# ProPrj_measure_boardd_2025-02-12.net
KiCad netlist of a schematic drawn in EasyEDA Pro
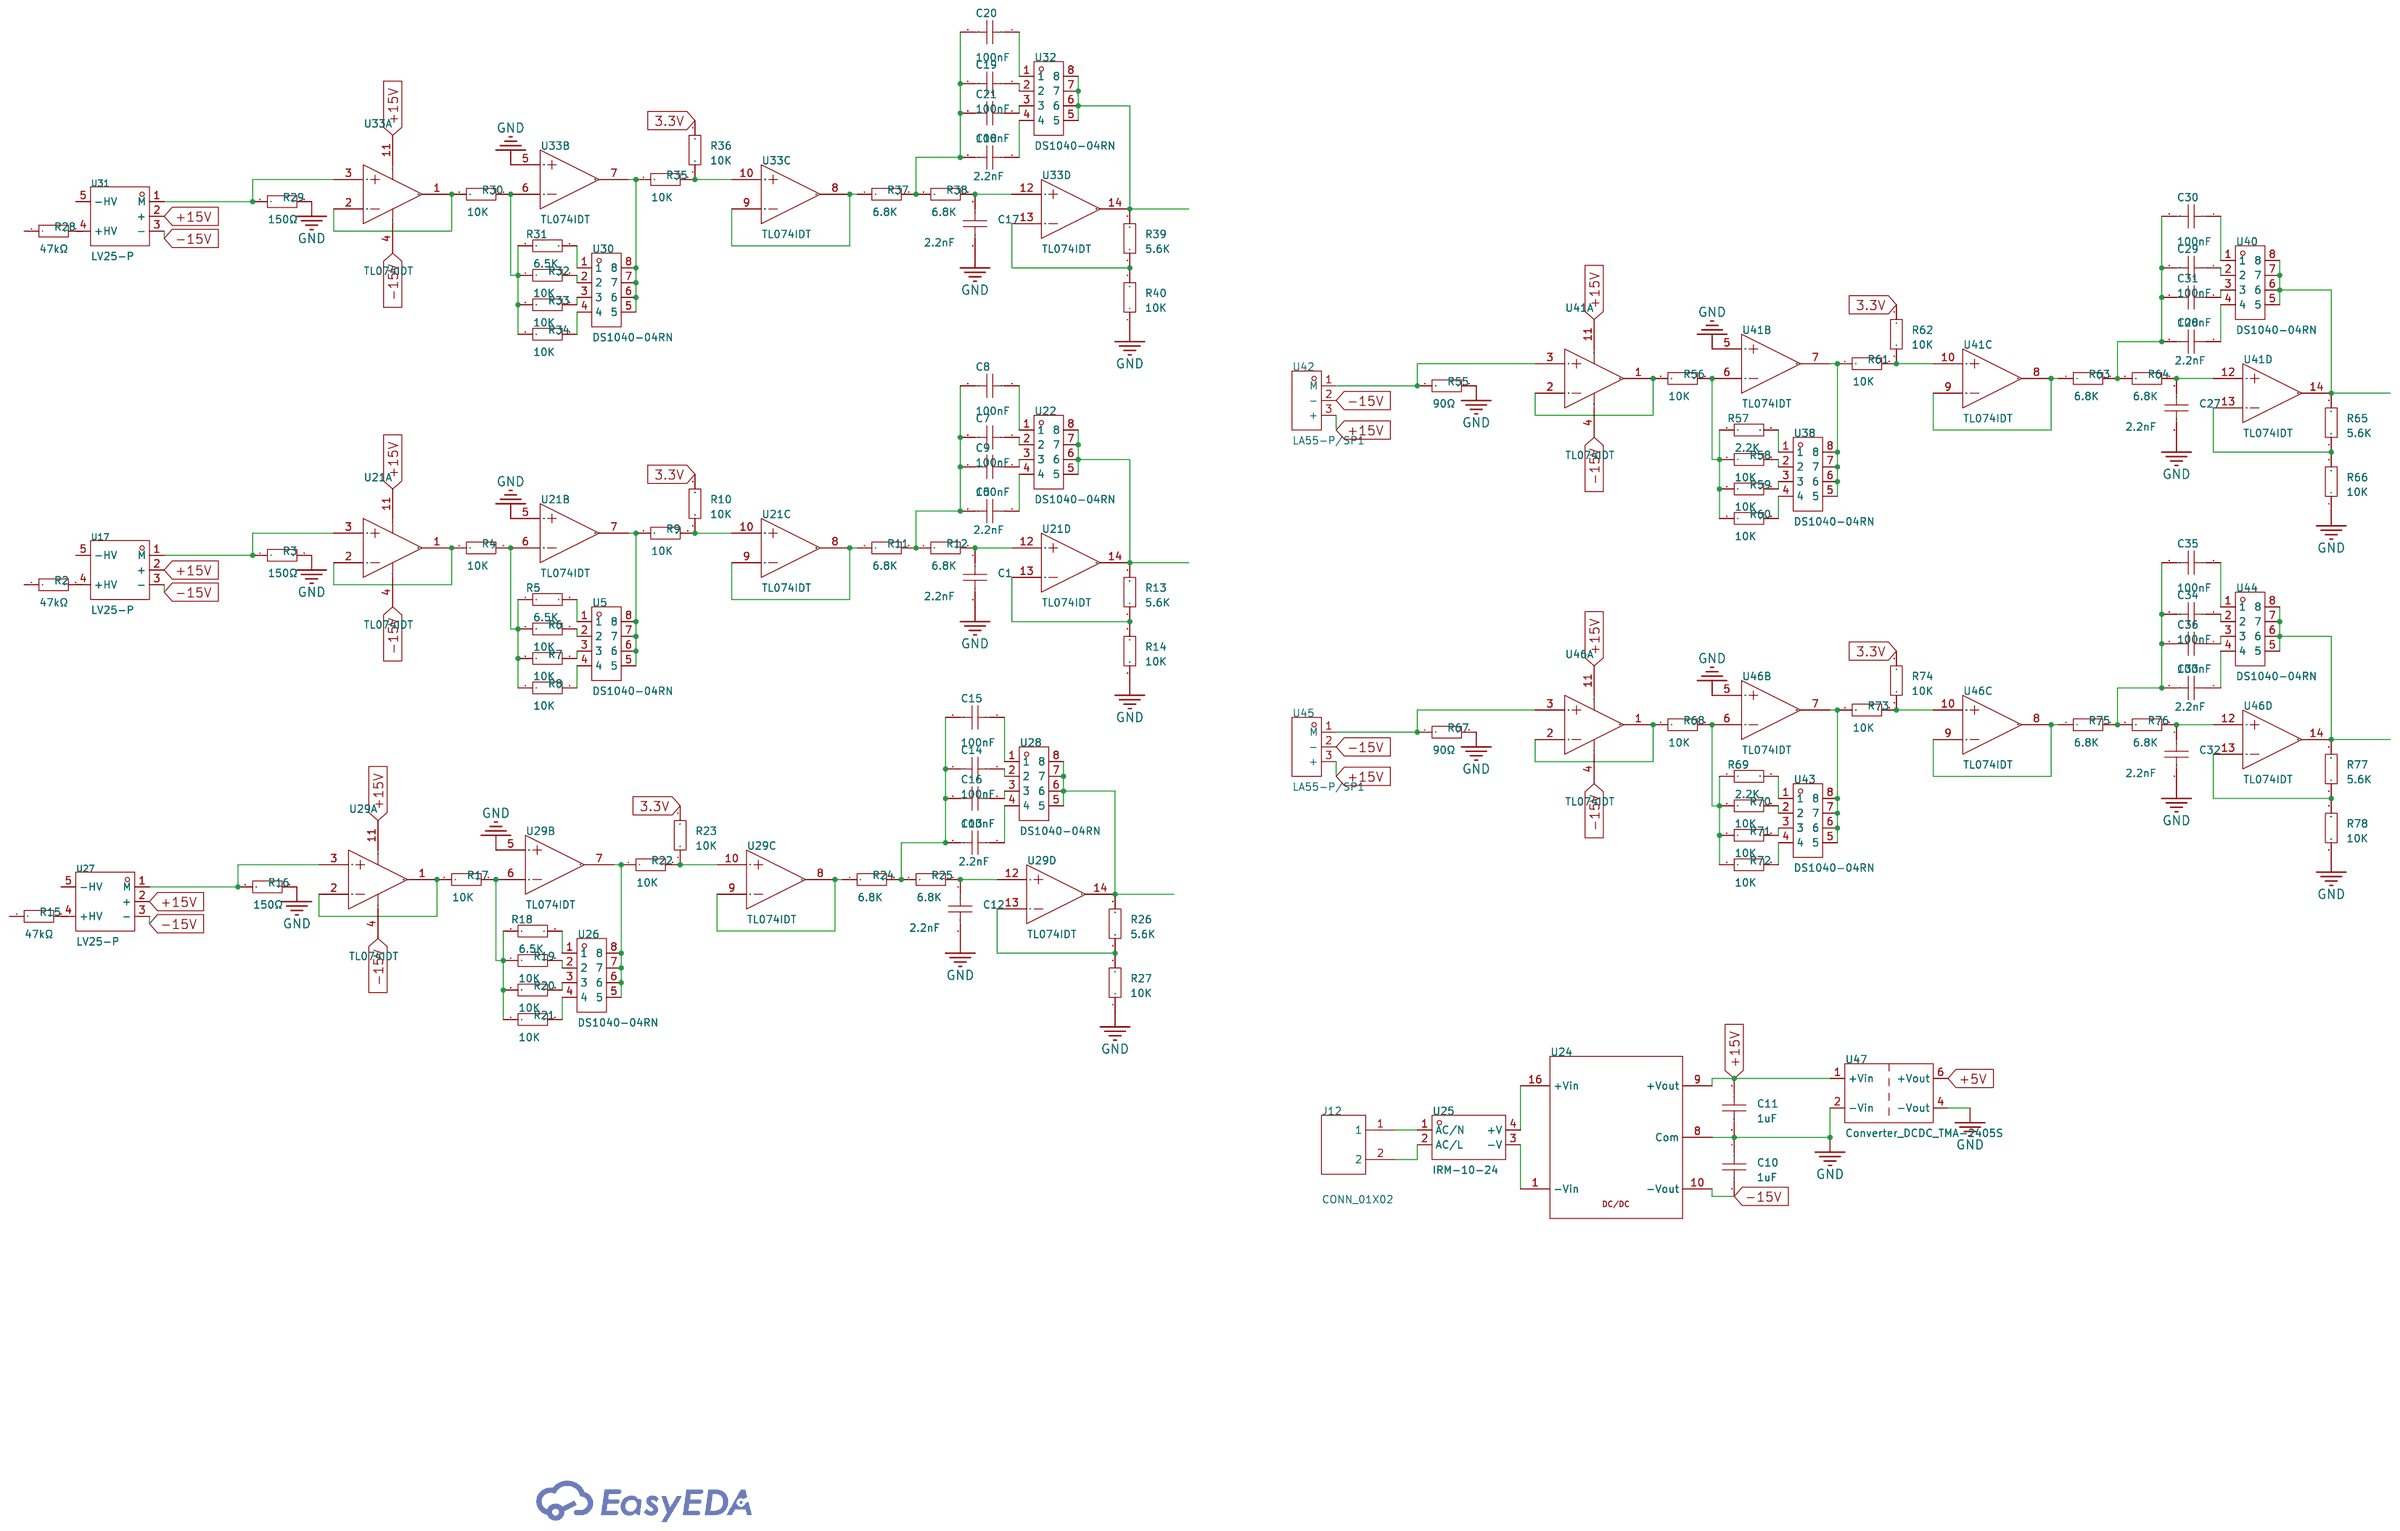
[diagram p0: schematic sheet]

(export (version "E")
  (design (tool "Eeschema 10.0.6"))
  (components
    (comp (ref "C1")
      (value "2.2nF")
      (footprint "easyedapro:C0805")
      (libsource (lib "easyedapro") (part "CAP"))
    )
    (comp (ref "C5")
      (value "2.2nF")
      (footprint "easyedapro:C0805")
      (libsource (lib "easyedapro") (part "CAP"))
    )
    (comp (ref "C7")
      (value "100nF")
      (footprint "easyedapro:C0805")
      (libsource (lib "easyedapro") (part "CAP"))
    )
    (comp (ref "C8")
      (value "100nF")
      (footprint "easyedapro:C0805")
      (libsource (lib "easyedapro") (part "CAP"))
    )
    (comp (ref "C9")
      (value "100nF")
      (footprint "easyedapro:C0805")
      (libsource (lib "easyedapro") (part "CAP"))
    )
    (comp (ref "C10")
      (value "1uF")
      (footprint "easyedapro:C0805")
      (libsource (lib "easyedapro") (part "CAP"))
    )
    (comp (ref "C11")
      (value "1uF")
      (footprint "easyedapro:C0805")
      (libsource (lib "easyedapro") (part "CAP"))
    )
    (comp (ref "C12")
      (value "2.2nF")
      (footprint "easyedapro:C0805")
      (libsource (lib "easyedapro") (part "CAP"))
    )
    (comp (ref "C13")
      (value "2.2nF")
      (footprint "easyedapro:C0805")
      (libsource (lib "easyedapro") (part "CAP"))
    )
    (comp (ref "C14")
      (value "100nF")
      (footprint "easyedapro:C0805")
      (libsource (lib "easyedapro") (part "CAP"))
    )
    (comp (ref "C15")
      (value "100nF")
      (footprint "easyedapro:C0805")
      (libsource (lib "easyedapro") (part "CAP"))
    )
    (comp (ref "C16")
      (value "100nF")
      (footprint "easyedapro:C0805")
      (libsource (lib "easyedapro") (part "CAP"))
    )
    (comp (ref "C17")
      (value "2.2nF")
      (footprint "easyedapro:C0805")
      (libsource (lib "easyedapro") (part "CAP"))
    )
    (comp (ref "C18")
      (value "2.2nF")
      (footprint "easyedapro:C0805")
      (libsource (lib "easyedapro") (part "CAP"))
    )
    (comp (ref "C19")
      (value "100nF")
      (footprint "easyedapro:C0805")
      (libsource (lib "easyedapro") (part "CAP"))
    )
    (comp (ref "C20")
      (value "100nF")
      (footprint "easyedapro:C0805")
      (libsource (lib "easyedapro") (part "CAP"))
    )
    (comp (ref "C21")
      (value "100nF")
      (footprint "easyedapro:C0805")
      (libsource (lib "easyedapro") (part "CAP"))
    )
    (comp (ref "C27")
      (value "2.2nF")
      (footprint "easyedapro:C0805")
      (libsource (lib "easyedapro") (part "CAP"))
    )
    (comp (ref "C28")
      (value "2.2nF")
      (footprint "easyedapro:C0805")
      (libsource (lib "easyedapro") (part "CAP"))
    )
    (comp (ref "C29")
      (value "100nF")
      (footprint "easyedapro:C0805")
      (libsource (lib "easyedapro") (part "CAP"))
    )
    (comp (ref "C30")
      (value "100nF")
      (footprint "easyedapro:C0805")
      (libsource (lib "easyedapro") (part "CAP"))
    )
    (comp (ref "C31")
      (value "100nF")
      (footprint "easyedapro:C0805")
      (libsource (lib "easyedapro") (part "CAP"))
    )
    (comp (ref "C32")
      (value "2.2nF")
      (footprint "easyedapro:C0805")
      (libsource (lib "easyedapro") (part "CAP"))
    )
    (comp (ref "C33")
      (value "2.2nF")
      (footprint "easyedapro:C0805")
      (libsource (lib "easyedapro") (part "CAP"))
    )
    (comp (ref "C34")
      (value "100nF")
      (footprint "easyedapro:C0805")
      (libsource (lib "easyedapro") (part "CAP"))
    )
    (comp (ref "C35")
      (value "100nF")
      (footprint "easyedapro:C0805")
      (libsource (lib "easyedapro") (part "CAP"))
    )
    (comp (ref "C36")
      (value "100nF")
      (footprint "easyedapro:C0805")
      (libsource (lib "easyedapro") (part "CAP"))
    )
    (comp (ref "J12")
      (value "CONN_01X02")
      (footprint "easyedapro:CONN-TH_2P-P3.81_1727010")
      (fields
        (field (name "Manufacturer Part") "1727010")
        (field (name "Manufacturer") "Phoenix Contact(菲尼克斯)")
      )
      (libsource (lib "easyedapro") (part "MKDS1/2-3.81-1727010"))
    )
    (comp (ref "R2")
      (value "47kΩ")
      (footprint "easyedapro:RES-TH_BD8.0-L24.5-P28.50-D0.8")
      (libsource (lib "easyedapro") (part "Res"))
    )
    (comp (ref "R3")
      (value "150Ω")
      (footprint "easyedapro:RES-TH_BD8.0-L24.5-P28.50-D0.8")
      (libsource (lib "easyedapro") (part "Res"))
    )
    (comp (ref "R4")
      (value "10K")
      (footprint "easyedapro:RES-TH_BD8.0-L24.5-P28.50-D0.8")
      (libsource (lib "easyedapro") (part "Res"))
    )
    (comp (ref "R5")
      (value "6.5K")
      (footprint "easyedapro:RES-TH_BD8.0-L24.5-P28.50-D0.8")
      (libsource (lib "easyedapro") (part "Res"))
    )
    (comp (ref "R6")
      (value "10K")
      (footprint "easyedapro:RES-TH_BD8.0-L24.5-P28.50-D0.8")
      (libsource (lib "easyedapro") (part "Res"))
    )
    (comp (ref "R7")
      (value "10K")
      (footprint "easyedapro:RES-TH_BD8.0-L24.5-P28.50-D0.8")
      (libsource (lib "easyedapro") (part "Res"))
    )
    (comp (ref "R8")
      (value "10K")
      (footprint "easyedapro:RES-TH_BD8.0-L24.5-P28.50-D0.8")
      (libsource (lib "easyedapro") (part "Res"))
    )
    (comp (ref "R9")
      (value "10K")
      (footprint "easyedapro:RES-TH_BD8.0-L24.5-P28.50-D0.8")
      (libsource (lib "easyedapro") (part "Res"))
    )
    (comp (ref "R10")
      (value "10K")
      (footprint "easyedapro:RES-TH_BD8.0-L24.5-P28.50-D0.8")
      (libsource (lib "easyedapro") (part "Res"))
    )
    (comp (ref "R11")
      (value "6.8K")
      (footprint "easyedapro:RES-TH_BD8.0-L24.5-P28.50-D0.8")
      (libsource (lib "easyedapro") (part "Res"))
    )
    (comp (ref "R12")
      (value "6.8K")
      (footprint "easyedapro:RES-TH_BD8.0-L24.5-P28.50-D0.8")
      (libsource (lib "easyedapro") (part "Res"))
    )
    (comp (ref "R13")
      (value "5.6K")
      (footprint "easyedapro:RES-TH_BD8.0-L24.5-P28.50-D0.8")
      (libsource (lib "easyedapro") (part "Res"))
    )
    (comp (ref "R14")
      (value "10K")
      (footprint "easyedapro:RES-TH_BD8.0-L24.5-P28.50-D0.8")
      (libsource (lib "easyedapro") (part "Res"))
    )
    (comp (ref "R15")
      (value "47kΩ")
      (footprint "easyedapro:RES-TH_BD8.0-L24.5-P28.50-D0.8")
      (libsource (lib "easyedapro") (part "Res"))
    )
    (comp (ref "R16")
      (value "150Ω")
      (footprint "easyedapro:RES-TH_BD8.0-L24.5-P28.50-D0.8")
      (libsource (lib "easyedapro") (part "Res"))
    )
    (comp (ref "R17")
      (value "10K")
      (footprint "easyedapro:RES-TH_BD8.0-L24.5-P28.50-D0.8")
      (libsource (lib "easyedapro") (part "Res"))
    )
    (comp (ref "R18")
      (value "6.5K")
      (footprint "easyedapro:RES-TH_BD8.0-L24.5-P28.50-D0.8")
      (libsource (lib "easyedapro") (part "Res"))
    )
    (comp (ref "R19")
      (value "10K")
      (footprint "easyedapro:RES-TH_BD8.0-L24.5-P28.50-D0.8")
      (libsource (lib "easyedapro") (part "Res"))
    )
    (comp (ref "R20")
      (value "10K")
      (footprint "easyedapro:RES-TH_BD8.0-L24.5-P28.50-D0.8")
      (libsource (lib "easyedapro") (part "Res"))
    )
    (comp (ref "R21")
      (value "10K")
      (footprint "easyedapro:RES-TH_BD8.0-L24.5-P28.50-D0.8")
      (libsource (lib "easyedapro") (part "Res"))
    )
    (comp (ref "R22")
      (value "10K")
      (footprint "easyedapro:RES-TH_BD8.0-L24.5-P28.50-D0.8")
      (libsource (lib "easyedapro") (part "Res"))
    )
    (comp (ref "R23")
      (value "10K")
      (footprint "easyedapro:RES-TH_BD8.0-L24.5-P28.50-D0.8")
      (libsource (lib "easyedapro") (part "Res"))
    )
    (comp (ref "R24")
      (value "6.8K")
      (footprint "easyedapro:RES-TH_BD8.0-L24.5-P28.50-D0.8")
      (libsource (lib "easyedapro") (part "Res"))
    )
    (comp (ref "R25")
      (value "6.8K")
      (footprint "easyedapro:RES-TH_BD8.0-L24.5-P28.50-D0.8")
      (libsource (lib "easyedapro") (part "Res"))
    )
    (comp (ref "R26")
      (value "5.6K")
      (footprint "easyedapro:RES-TH_BD8.0-L24.5-P28.50-D0.8")
      (libsource (lib "easyedapro") (part "Res"))
    )
    (comp (ref "R27")
      (value "10K")
      (footprint "easyedapro:RES-TH_BD8.0-L24.5-P28.50-D0.8")
      (libsource (lib "easyedapro") (part "Res"))
    )
    (comp (ref "R28")
      (value "47kΩ")
      (footprint "easyedapro:RES-TH_BD8.0-L24.5-P28.50-D0.8")
      (libsource (lib "easyedapro") (part "Res"))
    )
    (comp (ref "R29")
      (value "150Ω")
      (footprint "easyedapro:RES-TH_BD8.0-L24.5-P28.50-D0.8")
      (libsource (lib "easyedapro") (part "Res"))
    )
    (comp (ref "R30")
      (value "10K")
      (footprint "easyedapro:RES-TH_BD8.0-L24.5-P28.50-D0.8")
      (libsource (lib "easyedapro") (part "Res"))
    )
    (comp (ref "R31")
      (value "6.5K")
      (footprint "easyedapro:RES-TH_BD8.0-L24.5-P28.50-D0.8")
      (libsource (lib "easyedapro") (part "Res"))
    )
    (comp (ref "R32")
      (value "10K")
      (footprint "easyedapro:RES-TH_BD8.0-L24.5-P28.50-D0.8")
      (libsource (lib "easyedapro") (part "Res"))
    )
    (comp (ref "R33")
      (value "10K")
      (footprint "easyedapro:RES-TH_BD8.0-L24.5-P28.50-D0.8")
      (libsource (lib "easyedapro") (part "Res"))
    )
    (comp (ref "R34")
      (value "10K")
      (footprint "easyedapro:RES-TH_BD8.0-L24.5-P28.50-D0.8")
      (libsource (lib "easyedapro") (part "Res"))
    )
    (comp (ref "R35")
      (value "10K")
      (footprint "easyedapro:RES-TH_BD8.0-L24.5-P28.50-D0.8")
      (libsource (lib "easyedapro") (part "Res"))
    )
    (comp (ref "R36")
      (value "10K")
      (footprint "easyedapro:RES-TH_BD8.0-L24.5-P28.50-D0.8")
      (libsource (lib "easyedapro") (part "Res"))
    )
    (comp (ref "R37")
      (value "6.8K")
      (footprint "easyedapro:RES-TH_BD8.0-L24.5-P28.50-D0.8")
      (libsource (lib "easyedapro") (part "Res"))
    )
    (comp (ref "R38")
      (value "6.8K")
      (footprint "easyedapro:RES-TH_BD8.0-L24.5-P28.50-D0.8")
      (libsource (lib "easyedapro") (part "Res"))
    )
    (comp (ref "R39")
      (value "5.6K")
      (footprint "easyedapro:RES-TH_BD8.0-L24.5-P28.50-D0.8")
      (libsource (lib "easyedapro") (part "Res"))
    )
    (comp (ref "R40")
      (value "10K")
      (footprint "easyedapro:RES-TH_BD8.0-L24.5-P28.50-D0.8")
      (libsource (lib "easyedapro") (part "Res"))
    )
    (comp (ref "R55")
      (value "90Ω")
      (footprint "easyedapro:RES-TH_BD8.0-L24.5-P28.50-D0.8")
      (libsource (lib "easyedapro") (part "Res"))
    )
    (comp (ref "R56")
      (value "10K")
      (footprint "easyedapro:RES-TH_BD8.0-L24.5-P28.50-D0.8")
      (libsource (lib "easyedapro") (part "Res"))
    )
    (comp (ref "R57")
      (value "2.2K")
      (footprint "easyedapro:RES-TH_BD8.0-L24.5-P28.50-D0.8")
      (libsource (lib "easyedapro") (part "Res"))
    )
    (comp (ref "R58")
      (value "10K")
      (footprint "easyedapro:RES-TH_BD8.0-L24.5-P28.50-D0.8")
      (libsource (lib "easyedapro") (part "Res"))
    )
    (comp (ref "R59")
      (value "10K")
      (footprint "easyedapro:RES-TH_BD8.0-L24.5-P28.50-D0.8")
      (libsource (lib "easyedapro") (part "Res"))
    )
    (comp (ref "R60")
      (value "10K")
      (footprint "easyedapro:RES-TH_BD8.0-L24.5-P28.50-D0.8")
      (libsource (lib "easyedapro") (part "Res"))
    )
    (comp (ref "R61")
      (value "10K")
      (footprint "easyedapro:RES-TH_BD8.0-L24.5-P28.50-D0.8")
      (libsource (lib "easyedapro") (part "Res"))
    )
    (comp (ref "R62")
      (value "10K")
      (footprint "easyedapro:RES-TH_BD8.0-L24.5-P28.50-D0.8")
      (libsource (lib "easyedapro") (part "Res"))
    )
    (comp (ref "R63")
      (value "6.8K")
      (footprint "easyedapro:RES-TH_BD8.0-L24.5-P28.50-D0.8")
      (libsource (lib "easyedapro") (part "Res"))
    )
    (comp (ref "R64")
      (value "6.8K")
      (footprint "easyedapro:RES-TH_BD8.0-L24.5-P28.50-D0.8")
      (libsource (lib "easyedapro") (part "Res"))
    )
    (comp (ref "R65")
      (value "5.6K")
      (footprint "easyedapro:RES-TH_BD8.0-L24.5-P28.50-D0.8")
      (libsource (lib "easyedapro") (part "Res"))
    )
    (comp (ref "R66")
      (value "10K")
      (footprint "easyedapro:RES-TH_BD8.0-L24.5-P28.50-D0.8")
      (libsource (lib "easyedapro") (part "Res"))
    )
    (comp (ref "R67")
      (value "90Ω")
      (footprint "easyedapro:RES-TH_BD8.0-L24.5-P28.50-D0.8")
      (libsource (lib "easyedapro") (part "Res"))
    )
    (comp (ref "R68")
      (value "10K")
      (footprint "easyedapro:RES-TH_BD8.0-L24.5-P28.50-D0.8")
      (libsource (lib "easyedapro") (part "Res"))
    )
    (comp (ref "R69")
      (value "2.2K")
      (footprint "easyedapro:RES-TH_BD8.0-L24.5-P28.50-D0.8")
      (libsource (lib "easyedapro") (part "Res"))
    )
    (comp (ref "R70")
      (value "10K")
      (footprint "easyedapro:RES-TH_BD8.0-L24.5-P28.50-D0.8")
      (libsource (lib "easyedapro") (part "Res"))
    )
    (comp (ref "R71")
      (value "10K")
      (footprint "easyedapro:RES-TH_BD8.0-L24.5-P28.50-D0.8")
      (libsource (lib "easyedapro") (part "Res"))
    )
    (comp (ref "R72")
      (value "10K")
      (footprint "easyedapro:RES-TH_BD8.0-L24.5-P28.50-D0.8")
      (libsource (lib "easyedapro") (part "Res"))
    )
    (comp (ref "R73")
      (value "10K")
      (footprint "easyedapro:RES-TH_BD8.0-L24.5-P28.50-D0.8")
      (libsource (lib "easyedapro") (part "Res"))
    )
    (comp (ref "R74")
      (value "10K")
      (footprint "easyedapro:RES-TH_BD8.0-L24.5-P28.50-D0.8")
      (libsource (lib "easyedapro") (part "Res"))
    )
    (comp (ref "R75")
      (value "6.8K")
      (footprint "easyedapro:RES-TH_BD8.0-L24.5-P28.50-D0.8")
      (libsource (lib "easyedapro") (part "Res"))
    )
    (comp (ref "R76")
      (value "6.8K")
      (footprint "easyedapro:RES-TH_BD8.0-L24.5-P28.50-D0.8")
      (libsource (lib "easyedapro") (part "Res"))
    )
    (comp (ref "R77")
      (value "5.6K")
      (footprint "easyedapro:RES-TH_BD8.0-L24.5-P28.50-D0.8")
      (libsource (lib "easyedapro") (part "Res"))
    )
    (comp (ref "R78")
      (value "10K")
      (footprint "easyedapro:RES-TH_BD8.0-L24.5-P28.50-D0.8")
      (libsource (lib "easyedapro") (part "Res"))
    )
    (comp (ref "U5")
      (value "DS1040-04RN")
      (footprint "easyedapro:KEY-TH_DS1040-04RN")
      (description "Number of Positions:4Bit Lead Pitch:2.54mm Color:Red")
      (fields (field (name "Manufacturer") "CONNFLY"))
      (libsource (lib "easyedapro") (part "DS1040-04RN"))
    )
    (comp (ref "U17")
      (value "LV25-P")
      (footprint "easyedapro:SENSOR-TH_LV25-P")
      (fields (field (name "Manufacturer") "LEM(莱姆)"))
      (libsource (lib "easyedapro") (part "LV25-P"))
    )
    (comp (ref "U21")
      (value "TL074IDT")
      (footprint "easyedapro:SOIC-14_L8.7-W3.9-P1.27-LS6.0-BL")
      (fields (field (name "Manufacturer") "ST(意法半导体)"))
      (libsource (lib "easyedapro") (part "TL074IDT"))
    )
    (comp (ref "U22")
      (value "DS1040-04RN")
      (footprint "easyedapro:KEY-TH_DS1040-04RN")
      (description "Number of Positions:4Bit Lead Pitch:2.54mm Color:Red")
      (fields (field (name "Manufacturer") "CONNFLY"))
      (libsource (lib "easyedapro") (part "DS1040-04RN"))
    )
    (comp (ref "U24")
      (value "~")
      (footprint "easyedapro:TEL_8_SERIES")
      (libsource (lib "easyedapro") (part "TEL_8-2423"))
    )
    (comp (ref "U25")
      (value "IRM-10-24")
      (footprint "easyedapro:PWRM-TH_4P-L45.7-W25.4-P8.0")
      (fields (field (name "Manufacturer") "MW(明纬)"))
      (libsource (lib "easyedapro") (part "IRM-10-24_C5127809"))
    )
    (comp (ref "U26")
      (value "DS1040-04RN")
      (footprint "easyedapro:KEY-TH_DS1040-04RN")
      (description "Number of Positions:4Bit Lead Pitch:2.54mm Color:Red")
      (fields (field (name "Manufacturer") "CONNFLY"))
      (libsource (lib "easyedapro") (part "DS1040-04RN"))
    )
    (comp (ref "U27")
      (value "LV25-P")
      (footprint "easyedapro:SENSOR-TH_LV25-P")
      (fields (field (name "Manufacturer") "LEM(莱姆)"))
      (libsource (lib "easyedapro") (part "LV25-P"))
    )
    (comp (ref "U28")
      (value "DS1040-04RN")
      (footprint "easyedapro:KEY-TH_DS1040-04RN")
      (description "Number of Positions:4Bit Lead Pitch:2.54mm Color:Red")
      (fields (field (name "Manufacturer") "CONNFLY"))
      (libsource (lib "easyedapro") (part "DS1040-04RN"))
    )
    (comp (ref "U29")
      (value "TL074IDT")
      (footprint "easyedapro:SOIC-14_L8.7-W3.9-P1.27-LS6.0-BL")
      (fields (field (name "Manufacturer") "ST(意法半导体)"))
      (libsource (lib "easyedapro") (part "TL074IDT"))
    )
    (comp (ref "U30")
      (value "DS1040-04RN")
      (footprint "easyedapro:KEY-TH_DS1040-04RN")
      (description "Number of Positions:4Bit Lead Pitch:2.54mm Color:Red")
      (fields (field (name "Manufacturer") "CONNFLY"))
      (libsource (lib "easyedapro") (part "DS1040-04RN"))
    )
    (comp (ref "U31")
      (value "LV25-P")
      (footprint "easyedapro:SENSOR-TH_LV25-P")
      (fields (field (name "Manufacturer") "LEM(莱姆)"))
      (libsource (lib "easyedapro") (part "LV25-P"))
    )
    (comp (ref "U32")
      (value "DS1040-04RN")
      (footprint "easyedapro:KEY-TH_DS1040-04RN")
      (description "Number of Positions:4Bit Lead Pitch:2.54mm Color:Red")
      (fields (field (name "Manufacturer") "CONNFLY"))
      (libsource (lib "easyedapro") (part "DS1040-04RN"))
    )
    (comp (ref "U33")
      (value "TL074IDT")
      (footprint "easyedapro:SOIC-14_L8.7-W3.9-P1.27-LS6.0-BL")
      (fields (field (name "Manufacturer") "ST(意法半导体)"))
      (libsource (lib "easyedapro") (part "TL074IDT"))
    )
    (comp (ref "U38")
      (value "DS1040-04RN")
      (footprint "easyedapro:KEY-TH_DS1040-04RN")
      (description "Number of Positions:4Bit Lead Pitch:2.54mm Color:Red")
      (fields (field (name "Manufacturer") "CONNFLY"))
      (libsource (lib "easyedapro") (part "DS1040-04RN"))
    )
    (comp (ref "U40")
      (value "DS1040-04RN")
      (footprint "easyedapro:KEY-TH_DS1040-04RN")
      (description "Number of Positions:4Bit Lead Pitch:2.54mm Color:Red")
      (fields (field (name "Manufacturer") "CONNFLY"))
      (libsource (lib "easyedapro") (part "DS1040-04RN"))
    )
    (comp (ref "U41")
      (value "TL074IDT")
      (footprint "easyedapro:SOIC-14_L8.7-W3.9-P1.27-LS6.0-BL")
      (fields (field (name "Manufacturer") "ST(意法半导体)"))
      (libsource (lib "easyedapro") (part "TL074IDT"))
    )
    (comp (ref "U42")
      (value "LA55-P/SP1")
      (footprint "easyedapro:SENSOR-TH_LAXX-P")
      (fields (field (name "Manufacturer") "LEM(莱姆)"))
      (libsource (lib "easyedapro") (part "LA55-P/SP1"))
    )
    (comp (ref "U43")
      (value "DS1040-04RN")
      (footprint "easyedapro:KEY-TH_DS1040-04RN")
      (description "Number of Positions:4Bit Lead Pitch:2.54mm Color:Red")
      (fields (field (name "Manufacturer") "CONNFLY"))
      (libsource (lib "easyedapro") (part "DS1040-04RN"))
    )
    (comp (ref "U44")
      (value "DS1040-04RN")
      (footprint "easyedapro:KEY-TH_DS1040-04RN")
      (description "Number of Positions:4Bit Lead Pitch:2.54mm Color:Red")
      (fields (field (name "Manufacturer") "CONNFLY"))
      (libsource (lib "easyedapro") (part "DS1040-04RN"))
    )
    (comp (ref "U45")
      (value "LA55-P/SP1")
      (footprint "easyedapro:SENSOR-TH_LAXX-P")
      (fields (field (name "Manufacturer") "LEM(莱姆)"))
      (libsource (lib "easyedapro") (part "LA55-P/SP1"))
    )
    (comp (ref "U46")
      (value "TL074IDT")
      (footprint "easyedapro:SOIC-14_L8.7-W3.9-P1.27-LS6.0-BL")
      (fields (field (name "Manufacturer") "ST(意法半导体)"))
      (libsource (lib "easyedapro") (part "TL074IDT"))
    )
    (comp (ref "U47")
      (value "TMA-2405S")
      (footprint "easyedapro:Converter_DCDC:Converter_DCDC_TRACO_TMA-15xxS_24xxS_Single_THT")
      (libsource (lib "easyedapro") (part "Converter_DCDC_TMA-2405S"))
    )
  )
  (nets
    (net (code "1") (name "+5V") (class "Default")
      (node (ref "U47") (pin "6") (pinfunction "+Vout_6") (pintype "unspecified"))
    )
    (net (code "2") (name "+15V") (class "Default")
      (node (ref "C11") (pin "1") (pinfunction "1_1") (pintype "input"))
      (node (ref "U17") (pin "2") (pinfunction "+_2") (pintype "input"))
      (node (ref "U21") (pin "11") (pinfunction "VCC-_11") (pintype "unspecified"))
      (node (ref "U24") (pin "9") (pinfunction "+Vout_9") (pintype "unspecified"))
      (node (ref "U27") (pin "2") (pinfunction "+_2") (pintype "input"))
      (node (ref "U29") (pin "11") (pinfunction "VCC-_11") (pintype "unspecified"))
      (node (ref "U31") (pin "2") (pinfunction "+_2") (pintype "input"))
      (node (ref "U33") (pin "11") (pinfunction "VCC-_11") (pintype "unspecified"))
      (node (ref "U41") (pin "11") (pinfunction "VCC-_11") (pintype "unspecified"))
      (node (ref "U42") (pin "3") (pinfunction "+_3") (pintype "input"))
      (node (ref "U45") (pin "3") (pinfunction "+_3") (pintype "input"))
      (node (ref "U46") (pin "11") (pinfunction "VCC-_11") (pintype "unspecified"))
      (node (ref "U47") (pin "1") (pinfunction "+Vin_1") (pintype "unspecified"))
    )
    (net (code "3") (name "-15V") (class "Default")
      (node (ref "C10") (pin "2") (pinfunction "2_2") (pintype "input"))
      (node (ref "U17") (pin "3") (pinfunction "-_3") (pintype "input"))
      (node (ref "U21") (pin "4") (pinfunction "VCC+_4") (pintype "unspecified"))
      (node (ref "U24") (pin "10") (pinfunction "-Vout_10") (pintype "unspecified"))
      (node (ref "U27") (pin "3") (pinfunction "-_3") (pintype "input"))
      (node (ref "U29") (pin "4") (pinfunction "VCC+_4") (pintype "unspecified"))
      (node (ref "U31") (pin "3") (pinfunction "-_3") (pintype "input"))
      (node (ref "U33") (pin "4") (pinfunction "VCC+_4") (pintype "unspecified"))
      (node (ref "U41") (pin "4") (pinfunction "VCC+_4") (pintype "unspecified"))
      (node (ref "U42") (pin "2") (pinfunction "-_2") (pintype "input"))
      (node (ref "U45") (pin "2") (pinfunction "-_2") (pintype "input"))
      (node (ref "U46") (pin "4") (pinfunction "VCC+_4") (pintype "unspecified"))
    )
    (net (code "4") (name "3.3V") (class "Default")
      (node (ref "R10") (pin "2") (pinfunction "2_2") (pintype "input"))
      (node (ref "R23") (pin "2") (pinfunction "2_2") (pintype "input"))
      (node (ref "R36") (pin "2") (pinfunction "2_2") (pintype "input"))
      (node (ref "R62") (pin "2") (pinfunction "2_2") (pintype "input"))
      (node (ref "R74") (pin "2") (pinfunction "2_2") (pintype "input"))
    )
    (net (code "5") (name "GND") (class "Default")
      (node (ref "C1") (pin "2") (pinfunction "2_2") (pintype "input"))
      (node (ref "C10") (pin "1") (pinfunction "1_1") (pintype "input"))
      (node (ref "C11") (pin "2") (pinfunction "2_2") (pintype "input"))
      (node (ref "C12") (pin "2") (pinfunction "2_2") (pintype "input"))
      (node (ref "C17") (pin "2") (pinfunction "2_2") (pintype "input"))
      (node (ref "C27") (pin "2") (pinfunction "2_2") (pintype "input"))
      (node (ref "C32") (pin "2") (pinfunction "2_2") (pintype "input"))
      (node (ref "R14") (pin "1") (pinfunction "1_1") (pintype "input"))
      (node (ref "R16") (pin "2") (pinfunction "2_2") (pintype "input"))
      (node (ref "R27") (pin "1") (pinfunction "1_1") (pintype "input"))
      (node (ref "R29") (pin "2") (pinfunction "2_2") (pintype "input"))
      (node (ref "R3") (pin "2") (pinfunction "2_2") (pintype "input"))
      (node (ref "R40") (pin "1") (pinfunction "1_1") (pintype "input"))
      (node (ref "R55") (pin "2") (pinfunction "2_2") (pintype "input"))
      (node (ref "R66") (pin "1") (pinfunction "1_1") (pintype "input"))
      (node (ref "R67") (pin "2") (pinfunction "2_2") (pintype "input"))
      (node (ref "R78") (pin "1") (pinfunction "1_1") (pintype "input"))
      (node (ref "U21") (pin "5") (pinfunction "2IN+_5") (pintype "unspecified"))
      (node (ref "U24") (pin "8") (pinfunction "Com_8") (pintype "unspecified"))
      (node (ref "U29") (pin "5") (pinfunction "2IN+_5") (pintype "unspecified"))
      (node (ref "U33") (pin "5") (pinfunction "2IN+_5") (pintype "unspecified"))
      (node (ref "U41") (pin "5") (pinfunction "2IN+_5") (pintype "unspecified"))
      (node (ref "U46") (pin "5") (pinfunction "2IN+_5") (pintype "unspecified"))
      (node (ref "U47") (pin "2") (pinfunction "-Vin_2") (pintype "unspecified"))
      (node (ref "U47") (pin "4") (pinfunction "-Vout_4") (pintype "unspecified"))
    )
    (net (code "6") (name "Net-(C5-Pad1)") (class "Default")
      (node (ref "C5") (pin "1") (pinfunction "1_1") (pintype "input"))
      (node (ref "U22") (pin "4") (pinfunction "4_4") (pintype "unspecified"))
    )
    (net (code "7") (name "Net-(C5-Pad2)") (class "Default")
      (node (ref "C5") (pin "2") (pinfunction "2_2") (pintype "input"))
      (node (ref "C7") (pin "2") (pinfunction "2_2") (pintype "input"))
      (node (ref "C8") (pin "2") (pinfunction "2_2") (pintype "input"))
      (node (ref "C9") (pin "2") (pinfunction "2_2") (pintype "input"))
      (node (ref "R11") (pin "2") (pinfunction "2_2") (pintype "input"))
      (node (ref "R12") (pin "1") (pinfunction "1_1") (pintype "input"))
    )
    (net (code "8") (name "Net-(C7-Pad1)") (class "Default")
      (node (ref "C7") (pin "1") (pinfunction "1_1") (pintype "input"))
      (node (ref "U22") (pin "2") (pinfunction "2_2") (pintype "unspecified"))
    )
    (net (code "9") (name "Net-(C8-Pad1)") (class "Default")
      (node (ref "C8") (pin "1") (pinfunction "1_1") (pintype "input"))
      (node (ref "U22") (pin "1") (pinfunction "1_1") (pintype "unspecified"))
    )
    (net (code "10") (name "Net-(C9-Pad1)") (class "Default")
      (node (ref "C9") (pin "1") (pinfunction "1_1") (pintype "input"))
      (node (ref "U22") (pin "3") (pinfunction "3_3") (pintype "unspecified"))
    )
    (net (code "11") (name "Net-(C13-Pad1)") (class "Default")
      (node (ref "C13") (pin "1") (pinfunction "1_1") (pintype "input"))
      (node (ref "U28") (pin "4") (pinfunction "4_4") (pintype "unspecified"))
    )
    (net (code "12") (name "Net-(C13-Pad2)") (class "Default")
      (node (ref "C13") (pin "2") (pinfunction "2_2") (pintype "input"))
      (node (ref "C14") (pin "2") (pinfunction "2_2") (pintype "input"))
      (node (ref "C15") (pin "2") (pinfunction "2_2") (pintype "input"))
      (node (ref "C16") (pin "2") (pinfunction "2_2") (pintype "input"))
      (node (ref "R24") (pin "2") (pinfunction "2_2") (pintype "input"))
      (node (ref "R25") (pin "1") (pinfunction "1_1") (pintype "input"))
    )
    (net (code "13") (name "Net-(C14-Pad1)") (class "Default")
      (node (ref "C14") (pin "1") (pinfunction "1_1") (pintype "input"))
      (node (ref "U28") (pin "2") (pinfunction "2_2") (pintype "unspecified"))
    )
    (net (code "14") (name "Net-(C15-Pad1)") (class "Default")
      (node (ref "C15") (pin "1") (pinfunction "1_1") (pintype "input"))
      (node (ref "U28") (pin "1") (pinfunction "1_1") (pintype "unspecified"))
    )
    (net (code "15") (name "Net-(C16-Pad1)") (class "Default")
      (node (ref "C16") (pin "1") (pinfunction "1_1") (pintype "input"))
      (node (ref "U28") (pin "3") (pinfunction "3_3") (pintype "unspecified"))
    )
    (net (code "16") (name "Net-(C18-Pad1)") (class "Default")
      (node (ref "C18") (pin "1") (pinfunction "1_1") (pintype "input"))
      (node (ref "U32") (pin "4") (pinfunction "4_4") (pintype "unspecified"))
    )
    (net (code "17") (name "Net-(C18-Pad2)") (class "Default")
      (node (ref "C18") (pin "2") (pinfunction "2_2") (pintype "input"))
      (node (ref "C19") (pin "2") (pinfunction "2_2") (pintype "input"))
      (node (ref "C20") (pin "2") (pinfunction "2_2") (pintype "input"))
      (node (ref "C21") (pin "2") (pinfunction "2_2") (pintype "input"))
      (node (ref "R37") (pin "2") (pinfunction "2_2") (pintype "input"))
      (node (ref "R38") (pin "1") (pinfunction "1_1") (pintype "input"))
    )
    (net (code "18") (name "Net-(C19-Pad1)") (class "Default")
      (node (ref "C19") (pin "1") (pinfunction "1_1") (pintype "input"))
      (node (ref "U32") (pin "2") (pinfunction "2_2") (pintype "unspecified"))
    )
    (net (code "19") (name "Net-(C20-Pad1)") (class "Default")
      (node (ref "C20") (pin "1") (pinfunction "1_1") (pintype "input"))
      (node (ref "U32") (pin "1") (pinfunction "1_1") (pintype "unspecified"))
    )
    (net (code "20") (name "Net-(C21-Pad1)") (class "Default")
      (node (ref "C21") (pin "1") (pinfunction "1_1") (pintype "input"))
      (node (ref "U32") (pin "3") (pinfunction "3_3") (pintype "unspecified"))
    )
    (net (code "21") (name "Net-(C28-Pad1)") (class "Default")
      (node (ref "C28") (pin "1") (pinfunction "1_1") (pintype "input"))
      (node (ref "U40") (pin "4") (pinfunction "4_4") (pintype "unspecified"))
    )
    (net (code "22") (name "Net-(C28-Pad2)") (class "Default")
      (node (ref "C28") (pin "2") (pinfunction "2_2") (pintype "input"))
      (node (ref "C29") (pin "2") (pinfunction "2_2") (pintype "input"))
      (node (ref "C30") (pin "2") (pinfunction "2_2") (pintype "input"))
      (node (ref "C31") (pin "2") (pinfunction "2_2") (pintype "input"))
      (node (ref "R63") (pin "2") (pinfunction "2_2") (pintype "input"))
      (node (ref "R64") (pin "1") (pinfunction "1_1") (pintype "input"))
    )
    (net (code "23") (name "Net-(C29-Pad1)") (class "Default")
      (node (ref "C29") (pin "1") (pinfunction "1_1") (pintype "input"))
      (node (ref "U40") (pin "2") (pinfunction "2_2") (pintype "unspecified"))
    )
    (net (code "24") (name "Net-(C30-Pad1)") (class "Default")
      (node (ref "C30") (pin "1") (pinfunction "1_1") (pintype "input"))
      (node (ref "U40") (pin "1") (pinfunction "1_1") (pintype "unspecified"))
    )
    (net (code "25") (name "Net-(C31-Pad1)") (class "Default")
      (node (ref "C31") (pin "1") (pinfunction "1_1") (pintype "input"))
      (node (ref "U40") (pin "3") (pinfunction "3_3") (pintype "unspecified"))
    )
    (net (code "26") (name "Net-(C33-Pad1)") (class "Default")
      (node (ref "C33") (pin "1") (pinfunction "1_1") (pintype "input"))
      (node (ref "U44") (pin "4") (pinfunction "4_4") (pintype "unspecified"))
    )
    (net (code "27") (name "Net-(C33-Pad2)") (class "Default")
      (node (ref "C33") (pin "2") (pinfunction "2_2") (pintype "input"))
      (node (ref "C34") (pin "2") (pinfunction "2_2") (pintype "input"))
      (node (ref "C35") (pin "2") (pinfunction "2_2") (pintype "input"))
      (node (ref "C36") (pin "2") (pinfunction "2_2") (pintype "input"))
      (node (ref "R75") (pin "2") (pinfunction "2_2") (pintype "input"))
      (node (ref "R76") (pin "1") (pinfunction "1_1") (pintype "input"))
    )
    (net (code "28") (name "Net-(C34-Pad1)") (class "Default")
      (node (ref "C34") (pin "1") (pinfunction "1_1") (pintype "input"))
      (node (ref "U44") (pin "2") (pinfunction "2_2") (pintype "unspecified"))
    )
    (net (code "29") (name "Net-(C35-Pad1)") (class "Default")
      (node (ref "C35") (pin "1") (pinfunction "1_1") (pintype "input"))
      (node (ref "U44") (pin "1") (pinfunction "1_1") (pintype "unspecified"))
    )
    (net (code "30") (name "Net-(C36-Pad1)") (class "Default")
      (node (ref "C36") (pin "1") (pinfunction "1_1") (pintype "input"))
      (node (ref "U44") (pin "3") (pinfunction "3_3") (pintype "unspecified"))
    )
    (net (code "31") (name "Net-(R5-Pad2)") (class "Default")
      (node (ref "R5") (pin "2") (pinfunction "2_2") (pintype "input"))
      (node (ref "U5") (pin "1") (pinfunction "1_1") (pintype "unspecified"))
    )
    (net (code "32") (name "Net-(R6-Pad2)") (class "Default")
      (node (ref "R6") (pin "2") (pinfunction "2_2") (pintype "input"))
      (node (ref "U5") (pin "2") (pinfunction "2_2") (pintype "unspecified"))
    )
    (net (code "33") (name "Net-(R7-Pad2)") (class "Default")
      (node (ref "R7") (pin "2") (pinfunction "2_2") (pintype "input"))
      (node (ref "U5") (pin "3") (pinfunction "3_3") (pintype "unspecified"))
    )
    (net (code "34") (name "Net-(R8-Pad2)") (class "Default")
      (node (ref "R8") (pin "2") (pinfunction "2_2") (pintype "input"))
      (node (ref "U5") (pin "4") (pinfunction "4_4") (pintype "unspecified"))
    )
    (net (code "35") (name "Net-(R18-Pad2)") (class "Default")
      (node (ref "R18") (pin "2") (pinfunction "2_2") (pintype "input"))
      (node (ref "U26") (pin "1") (pinfunction "1_1") (pintype "unspecified"))
    )
    (net (code "36") (name "Net-(R19-Pad2)") (class "Default")
      (node (ref "R19") (pin "2") (pinfunction "2_2") (pintype "input"))
      (node (ref "U26") (pin "2") (pinfunction "2_2") (pintype "unspecified"))
    )
    (net (code "37") (name "Net-(R20-Pad2)") (class "Default")
      (node (ref "R20") (pin "2") (pinfunction "2_2") (pintype "input"))
      (node (ref "U26") (pin "3") (pinfunction "3_3") (pintype "unspecified"))
    )
    (net (code "38") (name "Net-(R21-Pad2)") (class "Default")
      (node (ref "R21") (pin "2") (pinfunction "2_2") (pintype "input"))
      (node (ref "U26") (pin "4") (pinfunction "4_4") (pintype "unspecified"))
    )
    (net (code "39") (name "Net-(R31-Pad2)") (class "Default")
      (node (ref "R31") (pin "2") (pinfunction "2_2") (pintype "input"))
      (node (ref "U30") (pin "1") (pinfunction "1_1") (pintype "unspecified"))
    )
    (net (code "40") (name "Net-(R32-Pad2)") (class "Default")
      (node (ref "R32") (pin "2") (pinfunction "2_2") (pintype "input"))
      (node (ref "U30") (pin "2") (pinfunction "2_2") (pintype "unspecified"))
    )
    (net (code "41") (name "Net-(R33-Pad2)") (class "Default")
      (node (ref "R33") (pin "2") (pinfunction "2_2") (pintype "input"))
      (node (ref "U30") (pin "3") (pinfunction "3_3") (pintype "unspecified"))
    )
    (net (code "42") (name "Net-(R34-Pad2)") (class "Default")
      (node (ref "R34") (pin "2") (pinfunction "2_2") (pintype "input"))
      (node (ref "U30") (pin "4") (pinfunction "4_4") (pintype "unspecified"))
    )
    (net (code "43") (name "Net-(R57-Pad2)") (class "Default")
      (node (ref "R57") (pin "2") (pinfunction "2_2") (pintype "input"))
      (node (ref "U38") (pin "1") (pinfunction "1_1") (pintype "unspecified"))
    )
    (net (code "44") (name "Net-(R58-Pad2)") (class "Default")
      (node (ref "R58") (pin "2") (pinfunction "2_2") (pintype "input"))
      (node (ref "U38") (pin "2") (pinfunction "2_2") (pintype "unspecified"))
    )
    (net (code "45") (name "Net-(R59-Pad2)") (class "Default")
      (node (ref "R59") (pin "2") (pinfunction "2_2") (pintype "input"))
      (node (ref "U38") (pin "3") (pinfunction "3_3") (pintype "unspecified"))
    )
    (net (code "46") (name "Net-(R60-Pad2)") (class "Default")
      (node (ref "R60") (pin "2") (pinfunction "2_2") (pintype "input"))
      (node (ref "U38") (pin "4") (pinfunction "4_4") (pintype "unspecified"))
    )
    (net (code "47") (name "Net-(R69-Pad2)") (class "Default")
      (node (ref "R69") (pin "2") (pinfunction "2_2") (pintype "input"))
      (node (ref "U43") (pin "1") (pinfunction "1_1") (pintype "unspecified"))
    )
    (net (code "48") (name "Net-(R70-Pad2)") (class "Default")
      (node (ref "R70") (pin "2") (pinfunction "2_2") (pintype "input"))
      (node (ref "U43") (pin "2") (pinfunction "2_2") (pintype "unspecified"))
    )
    (net (code "49") (name "Net-(R71-Pad2)") (class "Default")
      (node (ref "R71") (pin "2") (pinfunction "2_2") (pintype "input"))
      (node (ref "U43") (pin "3") (pinfunction "3_3") (pintype "unspecified"))
    )
    (net (code "50") (name "Net-(R72-Pad2)") (class "Default")
      (node (ref "R72") (pin "2") (pinfunction "2_2") (pintype "input"))
      (node (ref "U43") (pin "4") (pinfunction "4_4") (pintype "unspecified"))
    )
    (net (code "51") (name "Net-(U17-+HV)") (class "Default")
      (node (ref "R2") (pin "2") (pinfunction "2_2") (pintype "input"))
      (node (ref "U17") (pin "4") (pinfunction "+HV_4") (pintype "input"))
    )
    (net (code "52") (name "Net-(U17-M)") (class "Default")
      (node (ref "R3") (pin "1") (pinfunction "1_1") (pintype "input"))
      (node (ref "U17") (pin "1") (pinfunction "M_1") (pintype "input"))
      (node (ref "U21") (pin "3") (pinfunction "1IN+_3") (pintype "unspecified"))
    )
    (net (code "53") (name "Net-(U21A-1IN-)") (class "Default")
      (node (ref "R4") (pin "1") (pinfunction "1_1") (pintype "input"))
      (node (ref "U21") (pin "1") (pinfunction "1OUT_1") (pintype "unspecified"))
      (node (ref "U21") (pin "2") (pinfunction "1IN-_2") (pintype "unspecified"))
    )
    (net (code "54") (name "Net-(U21B-2IN-)") (class "Default")
      (node (ref "R4") (pin "2") (pinfunction "2_2") (pintype "input"))
      (node (ref "R5") (pin "1") (pinfunction "1_1") (pintype "input"))
      (node (ref "R6") (pin "1") (pinfunction "1_1") (pintype "input"))
      (node (ref "R7") (pin "1") (pinfunction "1_1") (pintype "input"))
      (node (ref "R8") (pin "1") (pinfunction "1_1") (pintype "input"))
      (node (ref "U21") (pin "6") (pinfunction "2IN-_6") (pintype "unspecified"))
    )
    (net (code "55") (name "Net-(U21B-2OUT)") (class "Default")
      (node (ref "R9") (pin "1") (pinfunction "1_1") (pintype "input"))
      (node (ref "U21") (pin "7") (pinfunction "2OUT_7") (pintype "unspecified"))
      (node (ref "U5") (pin "5") (pinfunction "5_5") (pintype "unspecified"))
      (node (ref "U5") (pin "6") (pinfunction "6_6") (pintype "unspecified"))
      (node (ref "U5") (pin "7") (pinfunction "7_7") (pintype "unspecified"))
      (node (ref "U5") (pin "8") (pinfunction "8_8") (pintype "unspecified"))
    )
    (net (code "56") (name "Net-(U21C-3IN+)") (class "Default")
      (node (ref "R10") (pin "1") (pinfunction "1_1") (pintype "input"))
      (node (ref "R9") (pin "2") (pinfunction "2_2") (pintype "input"))
      (node (ref "U21") (pin "10") (pinfunction "3IN+_10") (pintype "unspecified"))
    )
    (net (code "57") (name "Net-(U21C-3IN-)") (class "Default")
      (node (ref "R11") (pin "1") (pinfunction "1_1") (pintype "input"))
      (node (ref "U21") (pin "8") (pinfunction "3OUT_8") (pintype "unspecified"))
      (node (ref "U21") (pin "9") (pinfunction "3IN-_9") (pintype "unspecified"))
    )
    (net (code "58") (name "Net-(U21D-4IN+)") (class "Default")
      (node (ref "C1") (pin "1") (pinfunction "1_1") (pintype "input"))
      (node (ref "R12") (pin "2") (pinfunction "2_2") (pintype "input"))
      (node (ref "U21") (pin "12") (pinfunction "4IN+_12") (pintype "unspecified"))
    )
    (net (code "59") (name "Net-(U21D-4IN-)") (class "Default")
      (node (ref "R13") (pin "1") (pinfunction "1_1") (pintype "input"))
      (node (ref "R14") (pin "2") (pinfunction "2_2") (pintype "input"))
      (node (ref "U21") (pin "13") (pinfunction "4IN-_13") (pintype "unspecified"))
    )
    (net (code "60") (name "Net-(U21D-4OUT)") (class "Default")
      (node (ref "R13") (pin "2") (pinfunction "2_2") (pintype "input"))
      (node (ref "U21") (pin "14") (pinfunction "4OUT_14") (pintype "unspecified"))
      (node (ref "U22") (pin "5") (pinfunction "5_5") (pintype "unspecified"))
      (node (ref "U22") (pin "6") (pinfunction "6_6") (pintype "unspecified"))
      (node (ref "U22") (pin "7") (pinfunction "7_7") (pintype "unspecified"))
      (node (ref "U22") (pin "8") (pinfunction "8_8") (pintype "unspecified"))
    )
    (net (code "61") (name "Net-(U24-+Vin)") (class "Default")
      (node (ref "U24") (pin "16") (pinfunction "+Vin_16") (pintype "input"))
      (node (ref "U25") (pin "4") (pinfunction "+V_4") (pintype "unspecified"))
    )
    (net (code "62") (name "Net-(U24--Vin)") (class "Default")
      (node (ref "U24") (pin "1") (pinfunction "-Vin_1") (pintype "input"))
      (node (ref "U25") (pin "3") (pinfunction "-V_3") (pintype "unspecified"))
    )
    (net (code "63") (name "Net-(U25-AC{slash}L)") (class "Default")
      (node (ref "J12") (pin "2") (pinfunction "2_2") (pintype "unspecified"))
      (node (ref "U25") (pin "2") (pinfunction "AC/L_2") (pintype "unspecified"))
    )
    (net (code "64") (name "Net-(U25-AC{slash}N)") (class "Default")
      (node (ref "J12") (pin "1") (pinfunction "1_1") (pintype "unspecified"))
      (node (ref "U25") (pin "1") (pinfunction "AC/N_1") (pintype "unspecified"))
    )
    (net (code "65") (name "Net-(U27-+HV)") (class "Default")
      (node (ref "R15") (pin "2") (pinfunction "2_2") (pintype "input"))
      (node (ref "U27") (pin "4") (pinfunction "+HV_4") (pintype "input"))
    )
    (net (code "66") (name "Net-(U27-M)") (class "Default")
      (node (ref "R16") (pin "1") (pinfunction "1_1") (pintype "input"))
      (node (ref "U27") (pin "1") (pinfunction "M_1") (pintype "input"))
      (node (ref "U29") (pin "3") (pinfunction "1IN+_3") (pintype "unspecified"))
    )
    (net (code "67") (name "Net-(U29A-1IN-)") (class "Default")
      (node (ref "R17") (pin "1") (pinfunction "1_1") (pintype "input"))
      (node (ref "U29") (pin "1") (pinfunction "1OUT_1") (pintype "unspecified"))
      (node (ref "U29") (pin "2") (pinfunction "1IN-_2") (pintype "unspecified"))
    )
    (net (code "68") (name "Net-(U29B-2IN-)") (class "Default")
      (node (ref "R17") (pin "2") (pinfunction "2_2") (pintype "input"))
      (node (ref "R18") (pin "1") (pinfunction "1_1") (pintype "input"))
      (node (ref "R19") (pin "1") (pinfunction "1_1") (pintype "input"))
      (node (ref "R20") (pin "1") (pinfunction "1_1") (pintype "input"))
      (node (ref "R21") (pin "1") (pinfunction "1_1") (pintype "input"))
      (node (ref "U29") (pin "6") (pinfunction "2IN-_6") (pintype "unspecified"))
    )
    (net (code "69") (name "Net-(U29B-2OUT)") (class "Default")
      (node (ref "R22") (pin "1") (pinfunction "1_1") (pintype "input"))
      (node (ref "U26") (pin "5") (pinfunction "5_5") (pintype "unspecified"))
      (node (ref "U26") (pin "6") (pinfunction "6_6") (pintype "unspecified"))
      (node (ref "U26") (pin "7") (pinfunction "7_7") (pintype "unspecified"))
      (node (ref "U26") (pin "8") (pinfunction "8_8") (pintype "unspecified"))
      (node (ref "U29") (pin "7") (pinfunction "2OUT_7") (pintype "unspecified"))
    )
    (net (code "70") (name "Net-(U29C-3IN+)") (class "Default")
      (node (ref "R22") (pin "2") (pinfunction "2_2") (pintype "input"))
      (node (ref "R23") (pin "1") (pinfunction "1_1") (pintype "input"))
      (node (ref "U29") (pin "10") (pinfunction "3IN+_10") (pintype "unspecified"))
    )
    (net (code "71") (name "Net-(U29C-3IN-)") (class "Default")
      (node (ref "R24") (pin "1") (pinfunction "1_1") (pintype "input"))
      (node (ref "U29") (pin "8") (pinfunction "3OUT_8") (pintype "unspecified"))
      (node (ref "U29") (pin "9") (pinfunction "3IN-_9") (pintype "unspecified"))
    )
    (net (code "72") (name "Net-(U29D-4IN+)") (class "Default")
      (node (ref "C12") (pin "1") (pinfunction "1_1") (pintype "input"))
      (node (ref "R25") (pin "2") (pinfunction "2_2") (pintype "input"))
      (node (ref "U29") (pin "12") (pinfunction "4IN+_12") (pintype "unspecified"))
    )
    (net (code "73") (name "Net-(U29D-4IN-)") (class "Default")
      (node (ref "R26") (pin "1") (pinfunction "1_1") (pintype "input"))
      (node (ref "R27") (pin "2") (pinfunction "2_2") (pintype "input"))
      (node (ref "U29") (pin "13") (pinfunction "4IN-_13") (pintype "unspecified"))
    )
    (net (code "74") (name "Net-(U29D-4OUT)") (class "Default")
      (node (ref "R26") (pin "2") (pinfunction "2_2") (pintype "input"))
      (node (ref "U28") (pin "5") (pinfunction "5_5") (pintype "unspecified"))
      (node (ref "U28") (pin "6") (pinfunction "6_6") (pintype "unspecified"))
      (node (ref "U28") (pin "7") (pinfunction "7_7") (pintype "unspecified"))
      (node (ref "U28") (pin "8") (pinfunction "8_8") (pintype "unspecified"))
      (node (ref "U29") (pin "14") (pinfunction "4OUT_14") (pintype "unspecified"))
    )
    (net (code "75") (name "Net-(U31-+HV)") (class "Default")
      (node (ref "R28") (pin "2") (pinfunction "2_2") (pintype "input"))
      (node (ref "U31") (pin "4") (pinfunction "+HV_4") (pintype "input"))
    )
    (net (code "76") (name "Net-(U31-M)") (class "Default")
      (node (ref "R29") (pin "1") (pinfunction "1_1") (pintype "input"))
      (node (ref "U31") (pin "1") (pinfunction "M_1") (pintype "input"))
      (node (ref "U33") (pin "3") (pinfunction "1IN+_3") (pintype "unspecified"))
    )
    (net (code "77") (name "Net-(U33A-1IN-)") (class "Default")
      (node (ref "R30") (pin "1") (pinfunction "1_1") (pintype "input"))
      (node (ref "U33") (pin "1") (pinfunction "1OUT_1") (pintype "unspecified"))
      (node (ref "U33") (pin "2") (pinfunction "1IN-_2") (pintype "unspecified"))
    )
    (net (code "78") (name "Net-(U33B-2IN-)") (class "Default")
      (node (ref "R30") (pin "2") (pinfunction "2_2") (pintype "input"))
      (node (ref "R31") (pin "1") (pinfunction "1_1") (pintype "input"))
      (node (ref "R32") (pin "1") (pinfunction "1_1") (pintype "input"))
      (node (ref "R33") (pin "1") (pinfunction "1_1") (pintype "input"))
      (node (ref "R34") (pin "1") (pinfunction "1_1") (pintype "input"))
      (node (ref "U33") (pin "6") (pinfunction "2IN-_6") (pintype "unspecified"))
    )
    (net (code "79") (name "Net-(U33B-2OUT)") (class "Default")
      (node (ref "R35") (pin "1") (pinfunction "1_1") (pintype "input"))
      (node (ref "U30") (pin "5") (pinfunction "5_5") (pintype "unspecified"))
      (node (ref "U30") (pin "6") (pinfunction "6_6") (pintype "unspecified"))
      (node (ref "U30") (pin "7") (pinfunction "7_7") (pintype "unspecified"))
      (node (ref "U30") (pin "8") (pinfunction "8_8") (pintype "unspecified"))
      (node (ref "U33") (pin "7") (pinfunction "2OUT_7") (pintype "unspecified"))
    )
    (net (code "80") (name "Net-(U33C-3IN+)") (class "Default")
      (node (ref "R35") (pin "2") (pinfunction "2_2") (pintype "input"))
      (node (ref "R36") (pin "1") (pinfunction "1_1") (pintype "input"))
      (node (ref "U33") (pin "10") (pinfunction "3IN+_10") (pintype "unspecified"))
    )
    (net (code "81") (name "Net-(U33C-3IN-)") (class "Default")
      (node (ref "R37") (pin "1") (pinfunction "1_1") (pintype "input"))
      (node (ref "U33") (pin "8") (pinfunction "3OUT_8") (pintype "unspecified"))
      (node (ref "U33") (pin "9") (pinfunction "3IN-_9") (pintype "unspecified"))
    )
    (net (code "82") (name "Net-(U33D-4IN+)") (class "Default")
      (node (ref "C17") (pin "1") (pinfunction "1_1") (pintype "input"))
      (node (ref "R38") (pin "2") (pinfunction "2_2") (pintype "input"))
      (node (ref "U33") (pin "12") (pinfunction "4IN+_12") (pintype "unspecified"))
    )
    (net (code "83") (name "Net-(U33D-4IN-)") (class "Default")
      (node (ref "R39") (pin "1") (pinfunction "1_1") (pintype "input"))
      (node (ref "R40") (pin "2") (pinfunction "2_2") (pintype "input"))
      (node (ref "U33") (pin "13") (pinfunction "4IN-_13") (pintype "unspecified"))
    )
    (net (code "84") (name "Net-(U33D-4OUT)") (class "Default")
      (node (ref "R39") (pin "2") (pinfunction "2_2") (pintype "input"))
      (node (ref "U32") (pin "5") (pinfunction "5_5") (pintype "unspecified"))
      (node (ref "U32") (pin "6") (pinfunction "6_6") (pintype "unspecified"))
      (node (ref "U32") (pin "7") (pinfunction "7_7") (pintype "unspecified"))
      (node (ref "U32") (pin "8") (pinfunction "8_8") (pintype "unspecified"))
      (node (ref "U33") (pin "14") (pinfunction "4OUT_14") (pintype "unspecified"))
    )
    (net (code "85") (name "Net-(U41A-1IN+)") (class "Default")
      (node (ref "R55") (pin "1") (pinfunction "1_1") (pintype "input"))
      (node (ref "U41") (pin "3") (pinfunction "1IN+_3") (pintype "unspecified"))
      (node (ref "U42") (pin "1") (pinfunction "M_1") (pintype "input"))
    )
    (net (code "86") (name "Net-(U41A-1IN-)") (class "Default")
      (node (ref "R56") (pin "1") (pinfunction "1_1") (pintype "input"))
      (node (ref "U41") (pin "1") (pinfunction "1OUT_1") (pintype "unspecified"))
      (node (ref "U41") (pin "2") (pinfunction "1IN-_2") (pintype "unspecified"))
    )
    (net (code "87") (name "Net-(U41B-2IN-)") (class "Default")
      (node (ref "R56") (pin "2") (pinfunction "2_2") (pintype "input"))
      (node (ref "R57") (pin "1") (pinfunction "1_1") (pintype "input"))
      (node (ref "R58") (pin "1") (pinfunction "1_1") (pintype "input"))
      (node (ref "R59") (pin "1") (pinfunction "1_1") (pintype "input"))
      (node (ref "R60") (pin "1") (pinfunction "1_1") (pintype "input"))
      (node (ref "U41") (pin "6") (pinfunction "2IN-_6") (pintype "unspecified"))
    )
    (net (code "88") (name "Net-(U41B-2OUT)") (class "Default")
      (node (ref "R61") (pin "1") (pinfunction "1_1") (pintype "input"))
      (node (ref "U38") (pin "5") (pinfunction "5_5") (pintype "unspecified"))
      (node (ref "U38") (pin "6") (pinfunction "6_6") (pintype "unspecified"))
      (node (ref "U38") (pin "7") (pinfunction "7_7") (pintype "unspecified"))
      (node (ref "U38") (pin "8") (pinfunction "8_8") (pintype "unspecified"))
      (node (ref "U41") (pin "7") (pinfunction "2OUT_7") (pintype "unspecified"))
    )
    (net (code "89") (name "Net-(U41C-3IN+)") (class "Default")
      (node (ref "R61") (pin "2") (pinfunction "2_2") (pintype "input"))
      (node (ref "R62") (pin "1") (pinfunction "1_1") (pintype "input"))
      (node (ref "U41") (pin "10") (pinfunction "3IN+_10") (pintype "unspecified"))
    )
    (net (code "90") (name "Net-(U41C-3IN-)") (class "Default")
      (node (ref "R63") (pin "1") (pinfunction "1_1") (pintype "input"))
      (node (ref "U41") (pin "8") (pinfunction "3OUT_8") (pintype "unspecified"))
      (node (ref "U41") (pin "9") (pinfunction "3IN-_9") (pintype "unspecified"))
    )
    (net (code "91") (name "Net-(U41D-4IN+)") (class "Default")
      (node (ref "C27") (pin "1") (pinfunction "1_1") (pintype "input"))
      (node (ref "R64") (pin "2") (pinfunction "2_2") (pintype "input"))
      (node (ref "U41") (pin "12") (pinfunction "4IN+_12") (pintype "unspecified"))
    )
    (net (code "92") (name "Net-(U41D-4IN-)") (class "Default")
      (node (ref "R65") (pin "1") (pinfunction "1_1") (pintype "input"))
      (node (ref "R66") (pin "2") (pinfunction "2_2") (pintype "input"))
      (node (ref "U41") (pin "13") (pinfunction "4IN-_13") (pintype "unspecified"))
    )
    (net (code "93") (name "Net-(U41D-4OUT)") (class "Default")
      (node (ref "R65") (pin "2") (pinfunction "2_2") (pintype "input"))
      (node (ref "U40") (pin "5") (pinfunction "5_5") (pintype "unspecified"))
      (node (ref "U40") (pin "6") (pinfunction "6_6") (pintype "unspecified"))
      (node (ref "U40") (pin "7") (pinfunction "7_7") (pintype "unspecified"))
      (node (ref "U40") (pin "8") (pinfunction "8_8") (pintype "unspecified"))
      (node (ref "U41") (pin "14") (pinfunction "4OUT_14") (pintype "unspecified"))
    )
    (net (code "94") (name "Net-(U45-M)") (class "Default")
      (node (ref "R67") (pin "1") (pinfunction "1_1") (pintype "input"))
      (node (ref "U45") (pin "1") (pinfunction "M_1") (pintype "input"))
      (node (ref "U46") (pin "3") (pinfunction "1IN+_3") (pintype "unspecified"))
    )
    (net (code "95") (name "Net-(U46A-1IN-)") (class "Default")
      (node (ref "R68") (pin "1") (pinfunction "1_1") (pintype "input"))
      (node (ref "U46") (pin "1") (pinfunction "1OUT_1") (pintype "unspecified"))
      (node (ref "U46") (pin "2") (pinfunction "1IN-_2") (pintype "unspecified"))
    )
    (net (code "96") (name "Net-(U46B-2IN-)") (class "Default")
      (node (ref "R68") (pin "2") (pinfunction "2_2") (pintype "input"))
      (node (ref "R69") (pin "1") (pinfunction "1_1") (pintype "input"))
      (node (ref "R70") (pin "1") (pinfunction "1_1") (pintype "input"))
      (node (ref "R71") (pin "1") (pinfunction "1_1") (pintype "input"))
      (node (ref "R72") (pin "1") (pinfunction "1_1") (pintype "input"))
      (node (ref "U46") (pin "6") (pinfunction "2IN-_6") (pintype "unspecified"))
    )
    (net (code "97") (name "Net-(U46B-2OUT)") (class "Default")
      (node (ref "R73") (pin "1") (pinfunction "1_1") (pintype "input"))
      (node (ref "U43") (pin "5") (pinfunction "5_5") (pintype "unspecified"))
      (node (ref "U43") (pin "6") (pinfunction "6_6") (pintype "unspecified"))
      (node (ref "U43") (pin "7") (pinfunction "7_7") (pintype "unspecified"))
      (node (ref "U43") (pin "8") (pinfunction "8_8") (pintype "unspecified"))
      (node (ref "U46") (pin "7") (pinfunction "2OUT_7") (pintype "unspecified"))
    )
    (net (code "98") (name "Net-(U46C-3IN+)") (class "Default")
      (node (ref "R73") (pin "2") (pinfunction "2_2") (pintype "input"))
      (node (ref "R74") (pin "1") (pinfunction "1_1") (pintype "input"))
      (node (ref "U46") (pin "10") (pinfunction "3IN+_10") (pintype "unspecified"))
    )
    (net (code "99") (name "Net-(U46C-3IN-)") (class "Default")
      (node (ref "R75") (pin "1") (pinfunction "1_1") (pintype "input"))
      (node (ref "U46") (pin "8") (pinfunction "3OUT_8") (pintype "unspecified"))
      (node (ref "U46") (pin "9") (pinfunction "3IN-_9") (pintype "unspecified"))
    )
    (net (code "100") (name "Net-(U46D-4IN+)") (class "Default")
      (node (ref "C32") (pin "1") (pinfunction "1_1") (pintype "input"))
      (node (ref "R76") (pin "2") (pinfunction "2_2") (pintype "input"))
      (node (ref "U46") (pin "12") (pinfunction "4IN+_12") (pintype "unspecified"))
    )
    (net (code "101") (name "Net-(U46D-4IN-)") (class "Default")
      (node (ref "R77") (pin "1") (pinfunction "1_1") (pintype "input"))
      (node (ref "R78") (pin "2") (pinfunction "2_2") (pintype "input"))
      (node (ref "U46") (pin "13") (pinfunction "4IN-_13") (pintype "unspecified"))
    )
    (net (code "102") (name "Net-(U46D-4OUT)") (class "Default")
      (node (ref "R77") (pin "2") (pinfunction "2_2") (pintype "input"))
      (node (ref "U44") (pin "5") (pinfunction "5_5") (pintype "unspecified"))
      (node (ref "U44") (pin "6") (pinfunction "6_6") (pintype "unspecified"))
      (node (ref "U44") (pin "7") (pinfunction "7_7") (pintype "unspecified"))
      (node (ref "U44") (pin "8") (pinfunction "8_8") (pintype "unspecified"))
      (node (ref "U46") (pin "14") (pinfunction "4OUT_14") (pintype "unspecified"))
    )
    (net (code "103") (name "unconnected-(R2-Pad1)") (class "Default")
      (node (ref "R2") (pin "1") (pinfunction "1_1") (pintype "input"))
    )
    (net (code "104") (name "unconnected-(R15-Pad1)") (class "Default")
      (node (ref "R15") (pin "1") (pinfunction "1_1") (pintype "input"))
    )
    (net (code "105") (name "unconnected-(R28-Pad1)") (class "Default")
      (node (ref "R28") (pin "1") (pinfunction "1_1") (pintype "input"))
    )
    (net (code "106") (name "unconnected-(U17--HV-Pad5)") (class "Default")
      (node (ref "U17") (pin "5") (pinfunction "-HV_5") (pintype "input"))
    )
    (net (code "107") (name "unconnected-(U27--HV-Pad5)") (class "Default")
      (node (ref "U27") (pin "5") (pinfunction "-HV_5") (pintype "input"))
    )
    (net (code "108") (name "unconnected-(U31--HV-Pad5)") (class "Default")
      (node (ref "U31") (pin "5") (pinfunction "-HV_5") (pintype "input"))
    )
  )
)
